# RHD2132_headstage_16.net
KiCad netlist of a schematic drawn in EAGLE
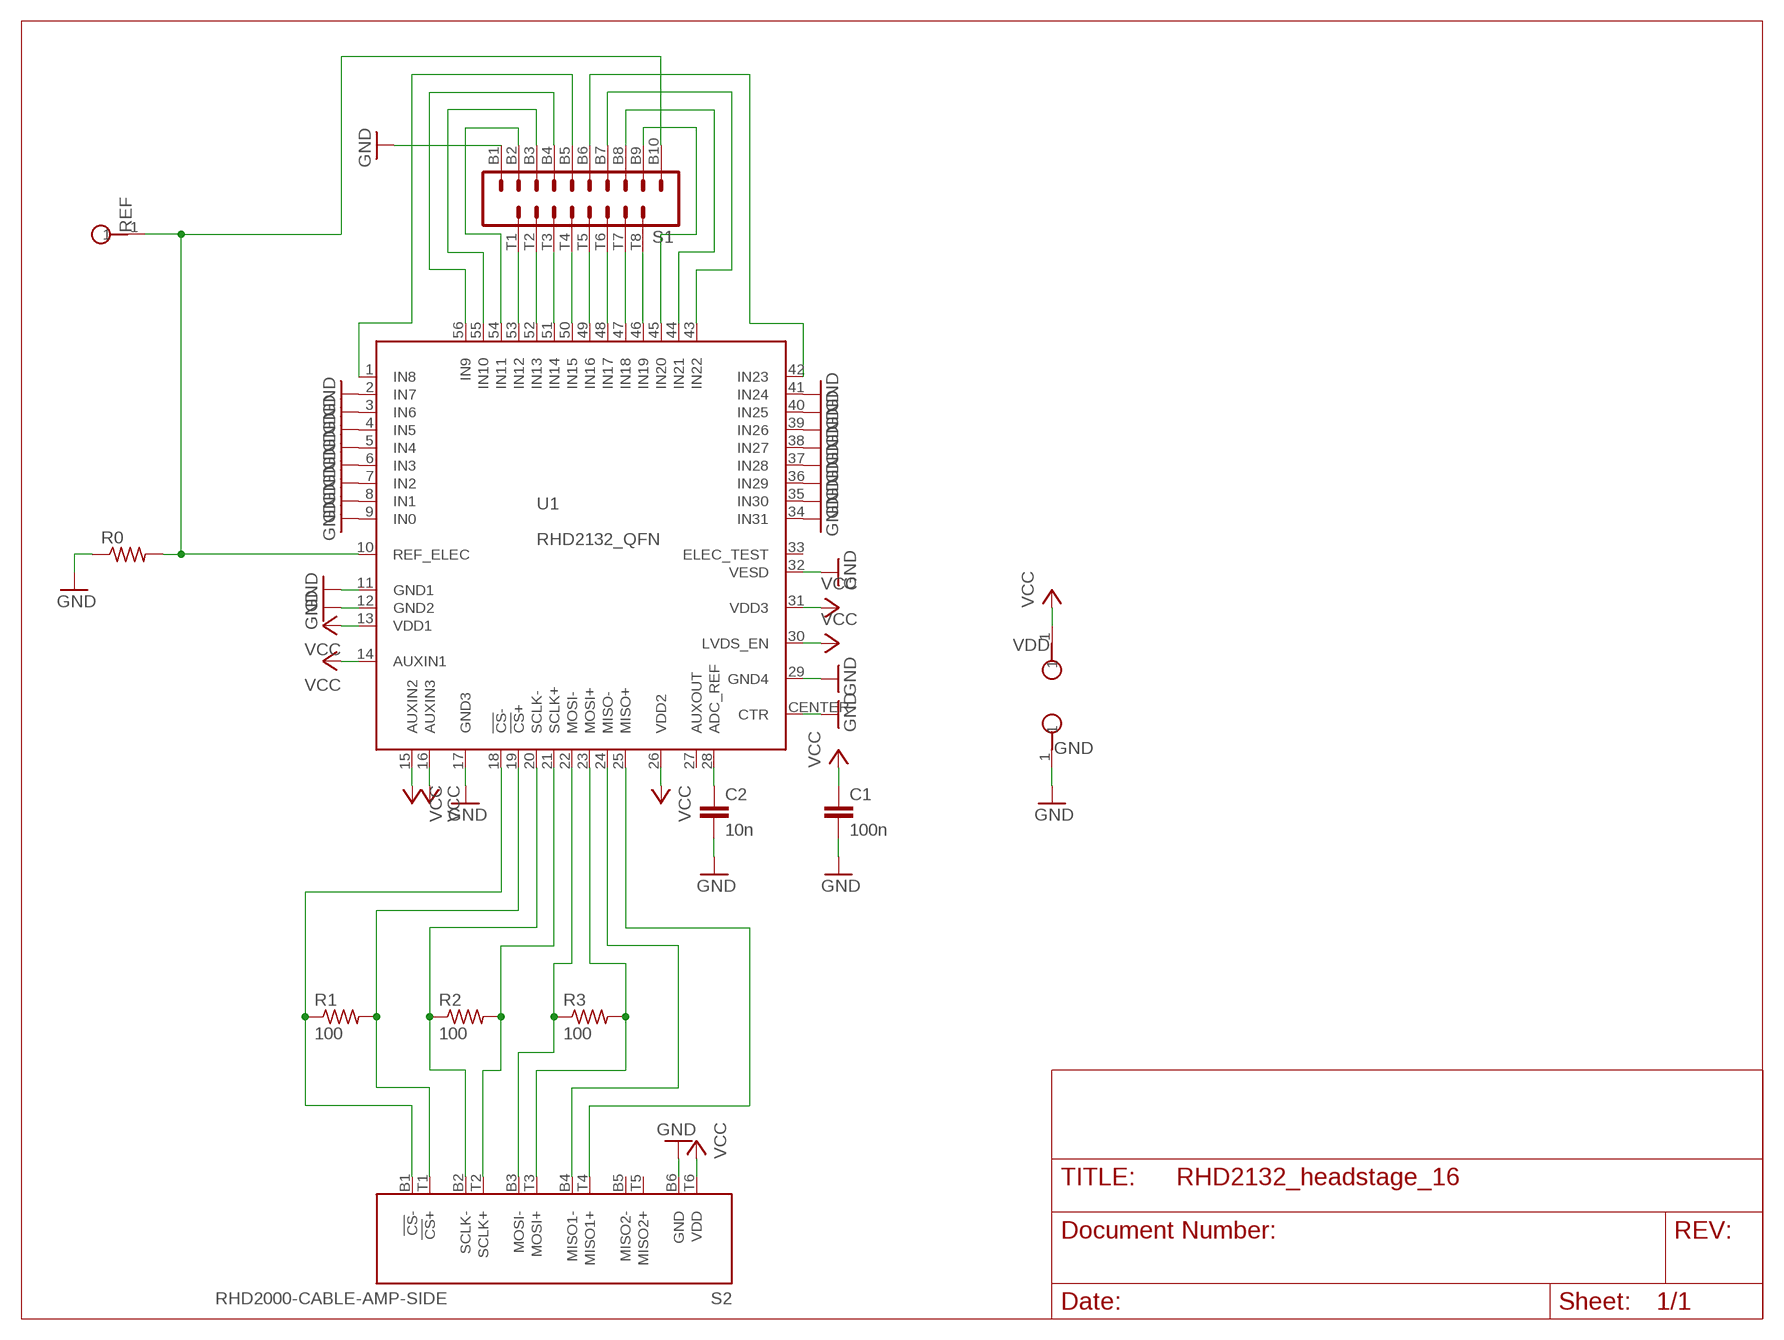
[diagram p0: schematic, sheet 1]

(export (version "E")
  (design (tool "Eeschema 10.0.6"))
  (components
    (comp (ref "C1")
      (value "100n")
      (footprint "eagle-import:0402")
      (libsource (lib "eagle-import") (part "C_0402"))
    )
    (comp (ref "C2")
      (value "10n")
      (footprint "eagle-import:0402")
      (libsource (lib "eagle-import") (part "C_0402"))
    )
    (comp (ref "GND")
      (value "TESTPOINT_SMALL")
      (footprint "eagle-import:TESTPOINT_SMALL")
      (libsource (lib "eagle-import") (part "TESTPOINT_SMALL"))
    )
    (comp (ref "R0")
      (value "R_0402")
      (footprint "eagle-import:0402")
      (libsource (lib "eagle-import") (part "R_0402"))
    )
    (comp (ref "R1")
      (value "100")
      (footprint "eagle-import:0402")
      (libsource (lib "eagle-import") (part "R_0402"))
    )
    (comp (ref "R2")
      (value "100")
      (footprint "eagle-import:0402")
      (libsource (lib "eagle-import") (part "R_0402"))
    )
    (comp (ref "R3")
      (value "100")
      (footprint "eagle-import:0402")
      (libsource (lib "eagle-import") (part "R_0402"))
    )
    (comp (ref "REF")
      (value "TESTPOINT_SMALL")
      (footprint "eagle-import:TESTPOINT_SMALL")
      (libsource (lib "eagle-import") (part "TESTPOINT_SMALL"))
    )
    (comp (ref "S1")
      (value "OMNETICS_A79041")
      (footprint "eagle-import:OMNETICS_A79041")
      (libsource (lib "eagle-import") (part "OMNETICS_A79041"))
    )
    (comp (ref "S2")
      (value "RHD2000-CABLE-AMP-SIDE")
      (footprint "eagle-import:OMNETICS_PZN-12-AA")
      (libsource (lib "eagle-import") (part "RHD2000-CABLE-AMP-SIDE"))
    )
    (comp (ref "U1")
      (value "RHD2132_QFN")
      (footprint "eagle-import:QFN56_8_X_8_LARGE")
      (libsource (lib "eagle-import") (part "RHD2132_QFN"))
    )
    (comp (ref "VDD")
      (value "TESTPOINT_SMALL")
      (footprint "eagle-import:TESTPOINT_SMALL")
      (libsource (lib "eagle-import") (part "TESTPOINT_SMALL"))
    )
  )
  (nets
    (net (code "1") (name "GND") (class "Default")
      (node (ref "C1") (pin "2") (pinfunction "2_2") (pintype "passive"))
      (node (ref "C2") (pin "2") (pinfunction "2_2") (pintype "passive"))
      (node (ref "GND") (pin "1") (pinfunction "1_1") (pintype "passive"))
      (node (ref "R0") (pin "1") (pinfunction "1_1") (pintype "passive"))
      (node (ref "S1") (pin "B1") (pinfunction "B1_B1") (pintype "passive"))
      (node (ref "S2") (pin "B6") (pinfunction "GND_B6") (pintype "power_in"))
      (node (ref "U1") (pin "11") (pinfunction "GND1_11") (pintype "power_in"))
      (node (ref "U1") (pin "12") (pinfunction "GND2_12") (pintype "power_in"))
      (node (ref "U1") (pin "17") (pinfunction "GND3_17") (pintype "power_in"))
      (node (ref "U1") (pin "2") (pinfunction "IN7_2") (pintype "input"))
      (node (ref "U1") (pin "29") (pinfunction "GND4_29") (pintype "power_in"))
      (node (ref "U1") (pin "3") (pinfunction "IN6_3") (pintype "input"))
      (node (ref "U1") (pin "32") (pinfunction "VESD_32") (pintype "power_in"))
      (node (ref "U1") (pin "34") (pinfunction "IN31_34") (pintype "input"))
      (node (ref "U1") (pin "35") (pinfunction "IN30_35") (pintype "input"))
      (node (ref "U1") (pin "36") (pinfunction "IN29_36") (pintype "input"))
      (node (ref "U1") (pin "37") (pinfunction "IN28_37") (pintype "input"))
      (node (ref "U1") (pin "38") (pinfunction "IN27_38") (pintype "input"))
      (node (ref "U1") (pin "39") (pinfunction "IN26_39") (pintype "input"))
      (node (ref "U1") (pin "4") (pinfunction "IN5_4") (pintype "input"))
      (node (ref "U1") (pin "40") (pinfunction "IN25_40") (pintype "input"))
      (node (ref "U1") (pin "41") (pinfunction "IN24_41") (pintype "input"))
      (node (ref "U1") (pin "5") (pinfunction "IN4_5") (pintype "input"))
      (node (ref "U1") (pin "6") (pinfunction "IN3_6") (pintype "input"))
      (node (ref "U1") (pin "7") (pinfunction "IN2_7") (pintype "input"))
      (node (ref "U1") (pin "8") (pinfunction "IN1_8") (pintype "input"))
      (node (ref "U1") (pin "9") (pinfunction "IN0_9") (pintype "input"))
      (node (ref "U1") (pin "CENTER") (pinfunction "CTR_CENTER") (pintype "power_in"))
    )
    (net (code "2") (name "Net-(S2-MISO1+)") (class "Default")
      (node (ref "S2") (pin "T4") (pinfunction "MISO1+_T4") (pintype "bidirectional"))
      (node (ref "U1") (pin "25") (pinfunction "MISO+_25") (pintype "output"))
    )
    (net (code "3") (name "Net-(S2-MISO1-)") (class "Default")
      (node (ref "S2") (pin "B4") (pinfunction "MISO1-_B4") (pintype "bidirectional"))
      (node (ref "U1") (pin "24") (pinfunction "MISO-_24") (pintype "output"))
    )
    (net (code "4") (name "Net-(S2-MOSI+)") (class "Default")
      (node (ref "R3") (pin "2") (pinfunction "2_2") (pintype "passive"))
      (node (ref "S2") (pin "T3") (pinfunction "MOSI+_T3") (pintype "bidirectional"))
      (node (ref "U1") (pin "23") (pinfunction "MOSI+_23") (pintype "input"))
    )
    (net (code "5") (name "Net-(S2-MOSI-)") (class "Default")
      (node (ref "R3") (pin "1") (pinfunction "1_1") (pintype "passive"))
      (node (ref "S2") (pin "B3") (pinfunction "MOSI-_B3") (pintype "bidirectional"))
      (node (ref "U1") (pin "22") (pinfunction "MOSI-_22") (pintype "input"))
    )
    (net (code "6") (name "Net-(S2-SCLK+)") (class "Default")
      (node (ref "R2") (pin "2") (pinfunction "2_2") (pintype "passive"))
      (node (ref "S2") (pin "T2") (pinfunction "SCLK+_T2") (pintype "bidirectional"))
      (node (ref "U1") (pin "21") (pinfunction "SCLK+_21") (pintype "input"))
    )
    (net (code "7") (name "Net-(S2-SCLK-)") (class "Default")
      (node (ref "R2") (pin "1") (pinfunction "1_1") (pintype "passive"))
      (node (ref "S2") (pin "B2") (pinfunction "SCLK-_B2") (pintype "bidirectional"))
      (node (ref "U1") (pin "20") (pinfunction "SCLK-_20") (pintype "input"))
    )
    (net (code "8") (name "Net-(S2-~{CS}+)") (class "Default")
      (node (ref "R1") (pin "2") (pinfunction "2_2") (pintype "passive"))
      (node (ref "S2") (pin "T1") (pinfunction "~{CS}+_T1") (pintype "bidirectional"))
      (node (ref "U1") (pin "19") (pinfunction "~{CS}+_19") (pintype "input"))
    )
    (net (code "9") (name "Net-(S2-~{CS}-)") (class "Default")
      (node (ref "R1") (pin "1") (pinfunction "1_1") (pintype "passive"))
      (node (ref "S2") (pin "B1") (pinfunction "~{CS}-_B1") (pintype "bidirectional"))
      (node (ref "U1") (pin "18") (pinfunction "~{CS}-_18") (pintype "input"))
    )
    (net (code "10") (name "Net-(U1-ADC_REF)") (class "Default")
      (node (ref "C2") (pin "1") (pinfunction "1_1") (pintype "passive"))
      (node (ref "U1") (pin "28") (pinfunction "ADC_REF_28") (pintype "passive"))
    )
    (net (code "11") (name "Net-(U1-IN8)") (class "Default")
      (node (ref "S1") (pin "B5") (pinfunction "B5_B5") (pintype "passive"))
      (node (ref "U1") (pin "1") (pinfunction "IN8_1") (pintype "input"))
    )
    (net (code "12") (name "Net-(U1-IN9)") (class "Default")
      (node (ref "S1") (pin "B4") (pinfunction "B4_B4") (pintype "passive"))
      (node (ref "U1") (pin "56") (pinfunction "IN9_56") (pintype "input"))
    )
    (net (code "13") (name "Net-(U1-IN10)") (class "Default")
      (node (ref "S1") (pin "B3") (pinfunction "B3_B3") (pintype "passive"))
      (node (ref "U1") (pin "55") (pinfunction "IN10_55") (pintype "input"))
    )
    (net (code "14") (name "Net-(U1-IN11)") (class "Default")
      (node (ref "S1") (pin "B2") (pinfunction "B2_B2") (pintype "passive"))
      (node (ref "U1") (pin "54") (pinfunction "IN11_54") (pintype "input"))
    )
    (net (code "15") (name "Net-(U1-IN12)") (class "Default")
      (node (ref "S1") (pin "T1") (pinfunction "T1_T1") (pintype "passive"))
      (node (ref "U1") (pin "53") (pinfunction "IN12_53") (pintype "input"))
    )
    (net (code "16") (name "Net-(U1-IN13)") (class "Default")
      (node (ref "S1") (pin "T2") (pinfunction "T2_T2") (pintype "passive"))
      (node (ref "U1") (pin "52") (pinfunction "IN13_52") (pintype "input"))
    )
    (net (code "17") (name "Net-(U1-IN14)") (class "Default")
      (node (ref "S1") (pin "T3") (pinfunction "T3_T3") (pintype "passive"))
      (node (ref "U1") (pin "51") (pinfunction "IN14_51") (pintype "input"))
    )
    (net (code "18") (name "Net-(U1-IN15)") (class "Default")
      (node (ref "S1") (pin "T4") (pinfunction "T4_T4") (pintype "passive"))
      (node (ref "U1") (pin "50") (pinfunction "IN15_50") (pintype "input"))
    )
    (net (code "19") (name "Net-(U1-IN16)") (class "Default")
      (node (ref "S1") (pin "T5") (pinfunction "T5_T5") (pintype "passive"))
      (node (ref "U1") (pin "49") (pinfunction "IN16_49") (pintype "input"))
    )
    (net (code "20") (name "Net-(U1-IN17)") (class "Default")
      (node (ref "S1") (pin "T6") (pinfunction "T6_T6") (pintype "passive"))
      (node (ref "U1") (pin "48") (pinfunction "IN17_48") (pintype "input"))
    )
    (net (code "21") (name "Net-(U1-IN18)") (class "Default")
      (node (ref "S1") (pin "T7") (pinfunction "T7_T7") (pintype "passive"))
      (node (ref "U1") (pin "47") (pinfunction "IN18_47") (pintype "input"))
    )
    (net (code "22") (name "Net-(U1-IN19)") (class "Default")
      (node (ref "S1") (pin "T8") (pinfunction "T8_T8") (pintype "passive"))
      (node (ref "U1") (pin "46") (pinfunction "IN19_46") (pintype "input"))
    )
    (net (code "23") (name "Net-(U1-IN20)") (class "Default")
      (node (ref "S1") (pin "B9") (pinfunction "B9_B9") (pintype "passive"))
      (node (ref "U1") (pin "45") (pinfunction "IN20_45") (pintype "input"))
    )
    (net (code "24") (name "Net-(U1-IN21)") (class "Default")
      (node (ref "S1") (pin "B8") (pinfunction "B8_B8") (pintype "passive"))
      (node (ref "U1") (pin "44") (pinfunction "IN21_44") (pintype "input"))
    )
    (net (code "25") (name "Net-(U1-IN22)") (class "Default")
      (node (ref "S1") (pin "B7") (pinfunction "B7_B7") (pintype "passive"))
      (node (ref "U1") (pin "43") (pinfunction "IN22_43") (pintype "input"))
    )
    (net (code "26") (name "Net-(U1-IN23)") (class "Default")
      (node (ref "S1") (pin "B6") (pinfunction "B6_B6") (pintype "passive"))
      (node (ref "U1") (pin "42") (pinfunction "IN23_42") (pintype "input"))
    )
    (net (code "27") (name "Net-(U1-REF_ELEC)") (class "Default")
      (node (ref "R0") (pin "2") (pinfunction "2_2") (pintype "passive"))
      (node (ref "REF") (pin "1") (pinfunction "1_1") (pintype "passive"))
      (node (ref "S1") (pin "B10") (pinfunction "B10_B10") (pintype "passive"))
      (node (ref "U1") (pin "10") (pinfunction "REF_ELEC_10") (pintype "input"))
    )
    (net (code "28") (name "VCC") (class "Default")
      (node (ref "C1") (pin "1") (pinfunction "1_1") (pintype "passive"))
      (node (ref "S2") (pin "T6") (pinfunction "VDD_T6") (pintype "bidirectional"))
      (node (ref "U1") (pin "13") (pinfunction "VDD1_13") (pintype "power_in"))
      (node (ref "U1") (pin "14") (pinfunction "AUXIN1_14") (pintype "input"))
      (node (ref "U1") (pin "15") (pinfunction "AUXIN2_15") (pintype "input"))
      (node (ref "U1") (pin "16") (pinfunction "AUXIN3_16") (pintype "input"))
      (node (ref "U1") (pin "26") (pinfunction "VDD2_26") (pintype "power_in"))
      (node (ref "U1") (pin "30") (pinfunction "LVDS_EN_30") (pintype "input"))
      (node (ref "U1") (pin "31") (pinfunction "VDD3_31") (pintype "power_in"))
      (node (ref "VDD") (pin "1") (pinfunction "1_1") (pintype "passive"))
    )
    (net (code "29") (name "unconnected-(S2-MISO2+-PadT5)") (class "Default")
      (node (ref "S2") (pin "T5") (pinfunction "MISO2+_T5") (pintype "bidirectional"))
    )
    (net (code "30") (name "unconnected-(S2-MISO2--PadB5)") (class "Default")
      (node (ref "S2") (pin "B5") (pinfunction "MISO2-_B5") (pintype "bidirectional"))
    )
    (net (code "31") (name "unconnected-(U1-AUXOUT-Pad27)") (class "Default")
      (node (ref "U1") (pin "27") (pinfunction "AUXOUT_27") (pintype "tri_state"))
    )
    (net (code "32") (name "unconnected-(U1-ELEC_TEST-Pad33)") (class "Default")
      (node (ref "U1") (pin "33") (pinfunction "ELEC_TEST_33") (pintype "input"))
    )
  )
)
